# Sch_Sh3.net
KiCad netlist of a schematic drawn in Altium Designer
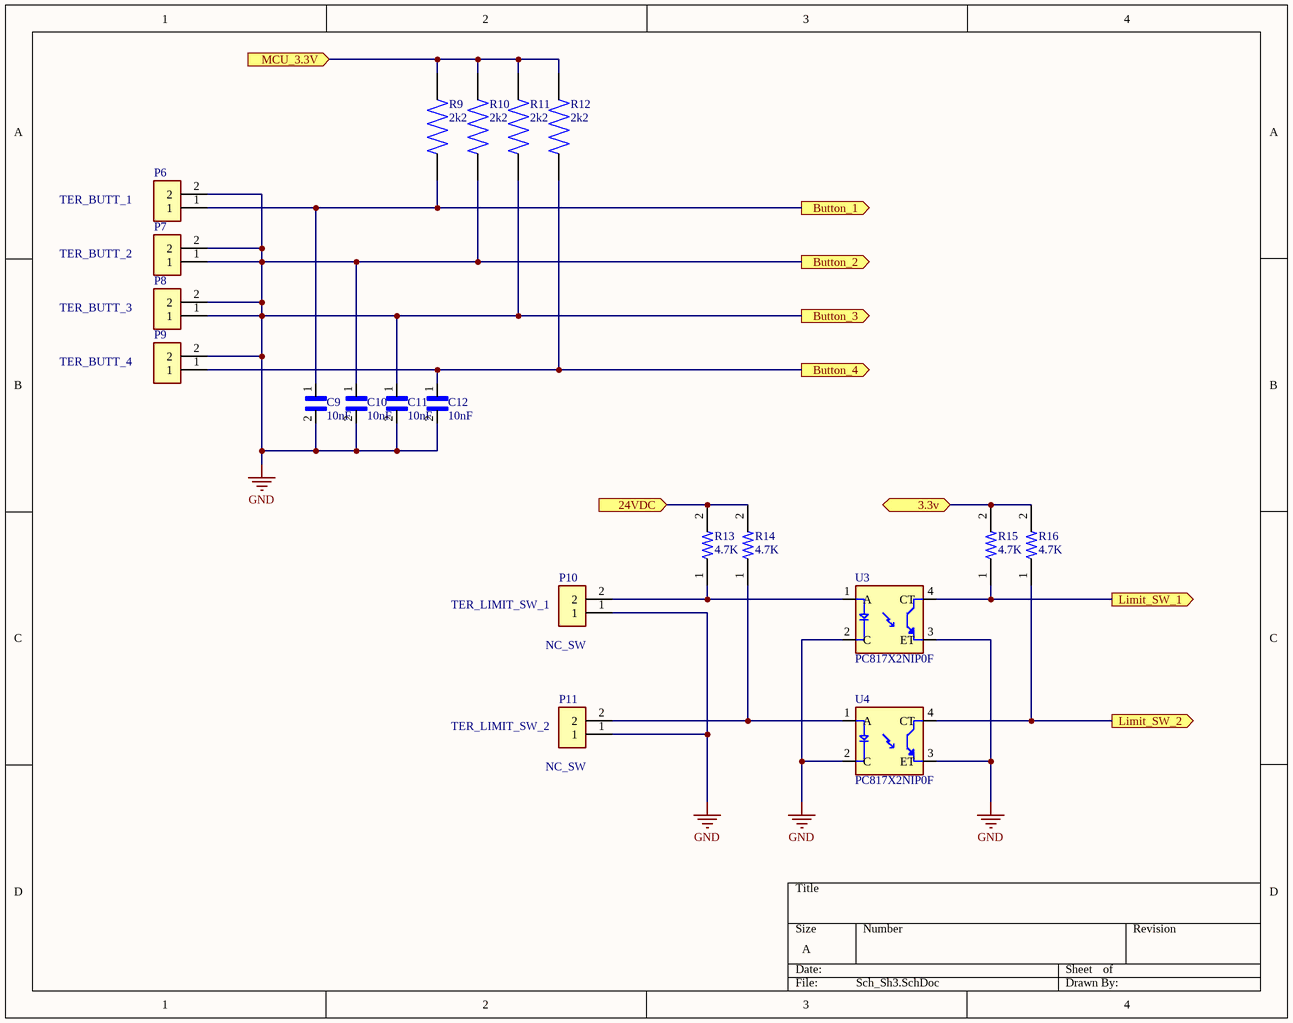
[diagram p0: Sch_Sh3.SchDoc]

(export (version "E")
  (design (tool "Eeschema 10.0.6"))
  (components
    (comp (ref "C9")
      (value "10nF")
      (footprint "CAPC1005X55N")
      (description "10000 pF Â±10% 50V Ceramic Capacitor X7R 0402 (1005 Metric)")
      (fields (field (name "MF") "Yageo") (field (name "MP") "CC0402KRX7R9BB103"))
      (libsource (lib "CC0402KRX7R9BB103") (part "CC0402KRX7R9BB103"))
    )
    (comp (ref "C10")
      (value "10nF")
      (footprint "CAPC1005X55N")
      (description "10000 pF Â±10% 50V Ceramic Capacitor X7R 0402 (1005 Metric)")
      (fields (field (name "MF") "Yageo") (field (name "MP") "CC0402KRX7R9BB103"))
      (libsource (lib "CC0402KRX7R9BB103") (part "CC0402KRX7R9BB103"))
    )
    (comp (ref "C11")
      (value "10nF")
      (footprint "CAPC1005X55N")
      (description "10000 pF Â±10% 50V Ceramic Capacitor X7R 0402 (1005 Metric)")
      (fields (field (name "MF") "Yageo") (field (name "MP") "CC0402KRX7R9BB103"))
      (libsource (lib "CC0402KRX7R9BB103") (part "CC0402KRX7R9BB103"))
    )
    (comp (ref "C12")
      (value "10nF")
      (footprint "CAPC1005X55N")
      (description "10000 pF Â±10% 50V Ceramic Capacitor X7R 0402 (1005 Metric)")
      (fields (field (name "MF") "Yageo") (field (name "MP") "CC0402KRX7R9BB103"))
      (libsource (lib "CC0402KRX7R9BB103") (part "CC0402KRX7R9BB103"))
    )
    (comp (ref "P6")
      (value "Button_1")
      (footprint "TE_282837-2")
      (description "Connector Terminal Blocks Receptacle 2 Position 5.08mm Solder Straight Thru-Hole 13.5A/Contact")
      (fields
        (field (name "MP") "282837-2")
        (field (name "MF") "TE Connectivity")
        (field (name "COMMENT_1") "TER_BUTT_1")
      )
      (libsource (lib "Con_TerminalBlock_2Pin_5.08mm") (part "282837-2"))
    )
    (comp (ref "P7")
      (value "282837-2")
      (footprint "TE_282837-2")
      (description "Connector Terminal Blocks Receptacle 2 Position 5.08mm Solder Straight Thru-Hole 13.5A/Contact")
      (fields (field (name "MF") "TE Connectivity") (field (name "COMMENT_1") "TER_BUTT_2"))
      (libsource (lib "Con_TerminalBlock_2Pin_5.08mm") (part "282837-2"))
    )
    (comp (ref "P8")
      (value "282837-2")
      (footprint "TE_282837-2")
      (description "Connector Terminal Blocks Receptacle 2 Position 5.08mm Solder Straight Thru-Hole 13.5A/Contact")
      (fields (field (name "MF") "TE Connectivity") (field (name "COMMENT_1") "TER_BUTT_3"))
      (libsource (lib "Con_TerminalBlock_2Pin_5.08mm") (part "282837-2"))
    )
    (comp (ref "P9")
      (value "282837-2")
      (footprint "TE_282837-2")
      (description "Connector Terminal Blocks Receptacle 2 Position 5.08mm Solder Straight Thru-Hole 13.5A/Contact")
      (fields (field (name "MF") "TE Connectivity") (field (name "COMMENT_1") "TER_BUTT_4"))
      (libsource (lib "Con_TerminalBlock_2Pin_5.08mm") (part "282837-2"))
    )
    (comp (ref "P10")
      (value "282837-2")
      (footprint "TE_282837-2")
      (description "Connector Terminal Blocks Receptacle 2 Position 5.08mm Solder Straight Thru-Hole 13.5A/Contact")
      (fields
        (field (name "MF") "TE Connectivity")
        (field (name "COMMENT_1") "TER_LIMIT_SW_1")
        (field (name "ALTIUM_UNNAMED_1") "NC_SW")
      )
      (libsource (lib "Con_TerminalBlock_2Pin_5.08mm") (part "282837-2"))
    )
    (comp (ref "P11")
      (value "282837-2")
      (footprint "TE_282837-2")
      (description "Connector Terminal Blocks Receptacle 2 Position 5.08mm Solder Straight Thru-Hole 13.5A/Contact")
      (fields
        (field (name "MF") "TE Connectivity")
        (field (name "COMMENT_1") "TER_LIMIT_SW_2")
        (field (name "ALTIUM_UNNAMED_1") "NC_SW")
      )
      (libsource (lib "Con_TerminalBlock_2Pin_5.08mm") (part "282837-2"))
    )
    (comp (ref "R9")
      (value "2k2")
      (footprint "RES_ERJ3EKF2201V")
      (description "2.2 kOhms 1% 0.1W, 1/10W Chip Resistor 0603 (1608 Metric) Automotive AEC-Q200 Thick Film")
      (fields (field (name "MP") "ERJ-3EKF2201V") (field (name "MF") "Panasonic"))
      (libsource (lib "ERJ3EKF2201V") (part "ERJ3EKF2201V"))
    )
    (comp (ref "R10")
      (value "2k2")
      (footprint "RES_ERJ3EKF2201V")
      (description "2.2 kOhms 1% 0.1W, 1/10W Chip Resistor 0603 (1608 Metric) Automotive AEC-Q200 Thick Film")
      (fields (field (name "MP") "ERJ-3EKF2201V") (field (name "MF") "Panasonic"))
      (libsource (lib "ERJ3EKF2201V") (part "ERJ3EKF2201V"))
    )
    (comp (ref "R11")
      (value "2k2")
      (footprint "RES_ERJ3EKF2201V")
      (description "2.2 kOhms 1% 0.1W, 1/10W Chip Resistor 0603 (1608 Metric) Automotive AEC-Q200 Thick Film")
      (fields (field (name "MP") "ERJ-3EKF2201V") (field (name "MF") "Panasonic"))
      (libsource (lib "ERJ3EKF2201V") (part "ERJ3EKF2201V"))
    )
    (comp (ref "R12")
      (value "2k2")
      (footprint "RES_ERJ3EKF2201V")
      (description "2.2 kOhms 1% 0.1W, 1/10W Chip Resistor 0603 (1608 Metric) Automotive AEC-Q200 Thick Film")
      (fields (field (name "MP") "ERJ-3EKF2201V") (field (name "MF") "Panasonic"))
      (libsource (lib "ERJ3EKF2201V") (part "ERJ3EKF2201V"))
    )
    (comp (ref "R13")
      (value "4.7K")
      (footprint "RESC1607X60N")
      (description "4.7 kOhms Â±1% 0.1W, 1/10W Chip Resistor 0603 _1608 Metric_ Moisture Resistant Thick Film")
      (fields (field (name "MP") "RC0603FR-074K7L") (field (name "MF") "Yageo"))
      (libsource (lib "RES_4.7_KRC0603FR-074K7L") (part "RC0603FR-074K7L"))
    )
    (comp (ref "R14")
      (value "4.7K")
      (footprint "RESC1607X60N")
      (description "4.7 kOhms Â±1% 0.1W, 1/10W Chip Resistor 0603 _1608 Metric_ Moisture Resistant Thick Film")
      (fields (field (name "MP") "RC0603FR-074K7L") (field (name "MF") "Yageo"))
      (libsource (lib "RES_4.7_KRC0603FR-074K7L") (part "RC0603FR-074K7L"))
    )
    (comp (ref "R15")
      (value "4.7K")
      (footprint "RESC1607X60N")
      (description "4.7 kOhms Â±1% 0.1W, 1/10W Chip Resistor 0603 _1608 Metric_ Moisture Resistant Thick Film")
      (fields (field (name "MP") "RC0603FR-074K7L") (field (name "MF") "Yageo"))
      (libsource (lib "RES_4.7_KRC0603FR-074K7L") (part "RC0603FR-074K7L"))
    )
    (comp (ref "R16")
      (value "4.7K")
      (footprint "RESC1607X60N")
      (description "4.7 kOhms Â±1% 0.1W, 1/10W Chip Resistor 0603 _1608 Metric_ Moisture Resistant Thick Film")
      (fields (field (name "MP") "RC0603FR-074K7L") (field (name "MF") "Yageo"))
      (libsource (lib "RES_4.7_KRC0603FR-074K7L") (part "RC0603FR-074K7L"))
    )
    (comp (ref "U3")
      (value "PC817X2NIP0F")
      (footprint "SOT254P975X400-4N")
      (description "Optoisolator Transistor Output 5000Vrms 1 Channel 4-SMD")
      (fields
        (field (name "MF") "Sharp Microelectronics")
        (field (name "DIGI-KEY_PART_NUMBER") "425-2192-2-ND")
      )
      (libsource (lib "PC817X2NIP0F") (part "PC817X2NIP0F"))
    )
    (comp (ref "U4")
      (value "PC817X2NIP0F")
      (footprint "SOT254P975X400-4N")
      (description "Optoisolator Transistor Output 5000Vrms 1 Channel 4-SMD")
      (fields
        (field (name "MF") "Sharp Microelectronics")
        (field (name "DIGI-KEY_PART_NUMBER") "425-2192-2-ND")
      )
      (libsource (lib "PC817X2NIP0F") (part "PC817X2NIP0F"))
    )
  )
  (nets
    (net (code "1") (name "/3.3v") (class "Default")
      (node (ref "R15") (pin "2") (pinfunction "2_2") (pintype "passive"))
      (node (ref "R16") (pin "2") (pinfunction "2_2") (pintype "passive"))
    )
    (net (code "2") (name "/24VDC") (class "Default")
      (node (ref "R13") (pin "2") (pinfunction "2_2") (pintype "passive"))
      (node (ref "R14") (pin "2") (pinfunction "2_2") (pintype "passive"))
    )
    (net (code "3") (name "/Button_1") (class "Default")
      (node (ref "C9") (pin "1") (pinfunction "1_1") (pintype "passive"))
      (node (ref "P6") (pin "1") (pinfunction "1_1") (pintype "passive"))
      (node (ref "R9") (pin "1") (pinfunction "1_1") (pintype "passive"))
    )
    (net (code "4") (name "/Button_4") (class "Default")
      (node (ref "C12") (pin "1") (pinfunction "1_1") (pintype "passive"))
      (node (ref "P9") (pin "1") (pinfunction "1_1") (pintype "passive"))
      (node (ref "R12") (pin "1") (pinfunction "1_1") (pintype "passive"))
    )
    (net (code "5") (name "/Limit_SW_1") (class "Default")
      (node (ref "R15") (pin "1") (pinfunction "1_1") (pintype "passive"))
      (node (ref "U3") (pin "4") (pinfunction "CT_4") (pintype "passive"))
    )
    (net (code "6") (name "/Limit_SW_2") (class "Default")
      (node (ref "R16") (pin "1") (pinfunction "1_1") (pintype "passive"))
      (node (ref "U4") (pin "4") (pinfunction "CT_4") (pintype "passive"))
    )
    (net (code "7") (name "/MCU_3.3V") (class "Default")
      (node (ref "R10") (pin "2") (pinfunction "2_2") (pintype "passive"))
      (node (ref "R11") (pin "2") (pinfunction "2_2") (pintype "passive"))
      (node (ref "R12") (pin "2") (pinfunction "2_2") (pintype "passive"))
      (node (ref "R9") (pin "2") (pinfunction "2_2") (pintype "passive"))
    )
    (net (code "8") (name "GND") (class "Default")
      (node (ref "C10") (pin "1") (pinfunction "1_1") (pintype "passive"))
      (node (ref "C10") (pin "2") (pinfunction "2_2") (pintype "passive"))
      (node (ref "C11") (pin "1") (pinfunction "1_1") (pintype "passive"))
      (node (ref "C11") (pin "2") (pinfunction "2_2") (pintype "passive"))
      (node (ref "C12") (pin "2") (pinfunction "2_2") (pintype "passive"))
      (node (ref "C9") (pin "2") (pinfunction "2_2") (pintype "passive"))
      (node (ref "P10") (pin "1") (pinfunction "1_1") (pintype "passive"))
      (node (ref "P11") (pin "1") (pinfunction "1_1") (pintype "passive"))
      (node (ref "P6") (pin "2") (pinfunction "2_2") (pintype "passive"))
      (node (ref "P7") (pin "1") (pinfunction "1_1") (pintype "passive"))
      (node (ref "P7") (pin "2") (pinfunction "2_2") (pintype "passive"))
      (node (ref "P8") (pin "1") (pinfunction "1_1") (pintype "passive"))
      (node (ref "P8") (pin "2") (pinfunction "2_2") (pintype "passive"))
      (node (ref "P9") (pin "2") (pinfunction "2_2") (pintype "passive"))
      (node (ref "R10") (pin "1") (pinfunction "1_1") (pintype "passive"))
      (node (ref "R11") (pin "1") (pinfunction "1_1") (pintype "passive"))
      (node (ref "U3") (pin "2") (pinfunction "C_2") (pintype "passive"))
      (node (ref "U3") (pin "3") (pinfunction "ET_3") (pintype "passive"))
      (node (ref "U4") (pin "2") (pinfunction "C_2") (pintype "passive"))
      (node (ref "U4") (pin "3") (pinfunction "ET_3") (pintype "passive"))
    )
    (net (code "9") (name "Net-(U3-A)") (class "Default")
      (node (ref "P10") (pin "2") (pinfunction "2_2") (pintype "passive"))
      (node (ref "R13") (pin "1") (pinfunction "1_1") (pintype "passive"))
      (node (ref "U3") (pin "1") (pinfunction "A_1") (pintype "passive"))
    )
    (net (code "10") (name "Net-(U4-A)") (class "Default")
      (node (ref "P11") (pin "2") (pinfunction "2_2") (pintype "passive"))
      (node (ref "R14") (pin "1") (pinfunction "1_1") (pintype "passive"))
      (node (ref "U4") (pin "1") (pinfunction "A_1") (pintype "passive"))
    )
  )
)
